# DMX_RP2040.net
KiCad netlist of a schematic drawn in Altium Designer
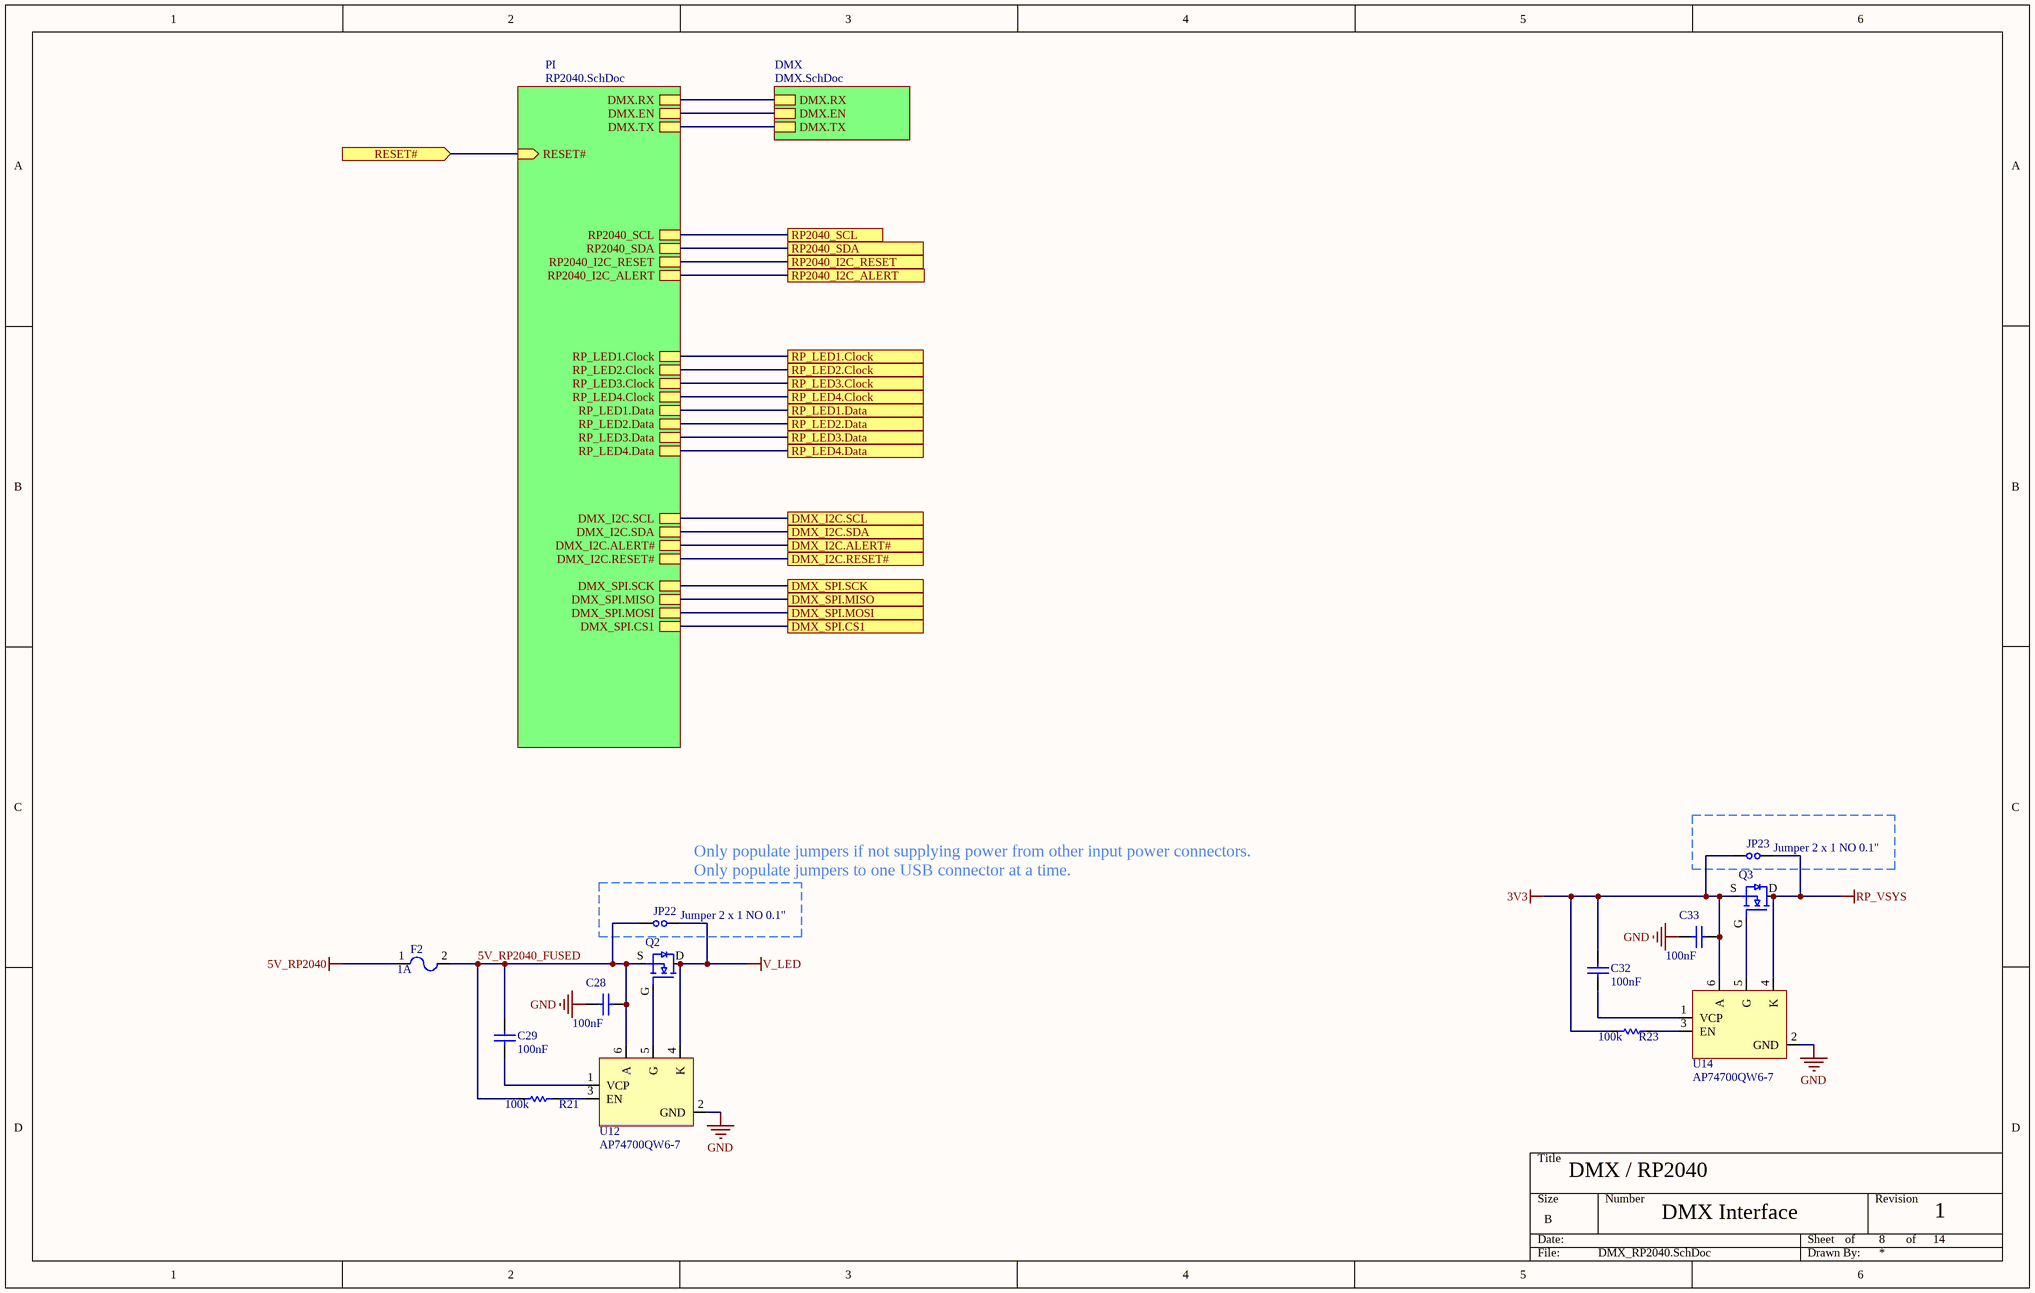
[diagram p0: DMX_RP2040.SchDoc]

(export (version "E")
  (design (tool "Eeschema 10.0.6"))
  (components
    (comp (ref "C28")
      (value "100nF")
      (footprint "CAPC1608X10N_0603_MED")
      (fields (field (name "Comment") "CC0603KRX7R0BB104"))
      (libsource (lib "Equus Computer Systems") (part "CAP-NP-2"))
    )
    (comp (ref "C29")
      (value "100nF")
      (footprint "CAPC1608X10N_0603_MED")
      (fields (field (name "Comment") "CC0603KRX7R0BB104"))
      (libsource (lib "Equus Computer Systems") (part "CAP-NP-2"))
    )
    (comp (ref "C32")
      (value "100nF")
      (footprint "CAPC1608X10N_0603_MED")
      (fields (field (name "Comment") "CC0603KRX7R0BB104"))
      (libsource (lib "Equus Computer Systems") (part "CAP-NP-2"))
    )
    (comp (ref "C33")
      (value "100nF")
      (footprint "CAPC1608X10N_0603_MED")
      (fields (field (name "Comment") "CC0603KRX7R0BB104"))
      (libsource (lib "Equus Computer Systems") (part "CAP-NP-2"))
    )
    (comp (ref "F2")
      (value "0ZCJ0100FF2E")
      (footprint "FUSE3216X04N_1206MED")
      (description "PTC Resettable Fuse, 6V, 0.055ohm, Surface Mount")
      (fields (field (name "CURRENT RATING") "1A"))
      (libsource (lib "Equus Computer Systems") (part "Fuse"))
    )
    (comp (ref "JP22")
      (value "Jumper 2 x 1 NO 0.1\"")
      (footprint "FP-M20-9990245-MFG")
      (libsource (lib "Equus Computer Systems") (part "Jumper 2 NO"))
    )
    (comp (ref "JP23")
      (value "Jumper 2 x 1 NO 0.1\"")
      (footprint "FP-M20-9990245-MFG")
      (libsource (lib "Equus Computer Systems") (part "Jumper 2 NO"))
    )
    (comp (ref "Q2")
      (value "DMN6075S-7")
      (footprint "FP-SOT23-MFG")
      (description "Single N-Channel 60 V 120 mOhm 12.3 nC 0.8 W Silicon Mosfet - SOT-23")
      (fields (field (name "POWER") "800mW"))
      (libsource (lib "Equus Computer Systems") (part "TRANS-MOSFET"))
    )
    (comp (ref "Q3")
      (value "DMN6075S-7")
      (footprint "FP-SOT23-MFG")
      (description "Single N-Channel 60 V 120 mOhm 12.3 nC 0.8 W Silicon Mosfet - SOT-23")
      (fields (field (name "POWER") "800mW"))
      (libsource (lib "Equus Computer Systems") (part "TRANS-MOSFET"))
    )
    (comp (ref "R21")
      (value "100k")
      (footprint "RESC1608X06N_0603_MED")
      (fields
        (field (name "POWER") "100mW")
        (field (name "TOLERANCE") "0.5%")
        (field (name "Comment") "RC0603DR-07100KL")
      )
      (libsource (lib "Equus Computer Systems") (part "RES-2"))
    )
    (comp (ref "R23")
      (value "100k")
      (footprint "RESC1608X06N_0603_MED")
      (fields
        (field (name "POWER") "100mW")
        (field (name "TOLERANCE") "0.5%")
        (field (name "Comment") "RC0603DR-07100KL")
      )
      (libsource (lib "Equus Computer Systems") (part "RES-2"))
    )
    (comp (ref "U12")
      (value "AP74700QW6-7")
      (footprint "SOT95P285X130-6N")
      (description "ORController N-Channel Single Automotive AEC-Q100 6-Pin SOT-26 T/R")
      (libsource (lib "Equus Computer Systems") (part "AP74700QW6-7-Symbol-1"))
    )
    (comp (ref "U14")
      (value "AP74700QW6-7")
      (footprint "SOT95P285X130-6N")
      (description "ORController N-Channel Single Automotive AEC-Q100 6-Pin SOT-26 T/R")
      (libsource (lib "Equus Computer Systems") (part "AP74700QW6-7-Symbol-1"))
    )
  )
  (nets
    (net (code "1") (name "/5V_RP2040_FUSED") (class "Default")
      (node (ref "C28") (pin "1") (pinfunction "1_1") (pintype "passive"))
      (node (ref "C29") (pin "2") (pinfunction "2_2") (pintype "passive"))
      (node (ref "F2") (pin "2") (pinfunction "2_2") (pintype "passive"))
      (node (ref "JP22") (pin "1") (pinfunction "1_1") (pintype "passive"))
      (node (ref "Q2") (pin "S") (pinfunction "S_S") (pintype "passive"))
      (node (ref "R21") (pin "1") (pinfunction "1_1") (pintype "passive"))
      (node (ref "U12") (pin "6") (pinfunction "A_6") (pintype "passive"))
    )
    (net (code "26") (name "3V3") (class "Default")
      (node (ref "C32") (pin "2") (pinfunction "2_2") (pintype "passive"))
      (node (ref "C33") (pin "1") (pinfunction "1_1") (pintype "passive"))
      (node (ref "JP23") (pin "1") (pinfunction "1_1") (pintype "passive"))
      (node (ref "Q3") (pin "S") (pinfunction "S_S") (pintype "passive"))
      (node (ref "R23") (pin "2") (pinfunction "2_2") (pintype "passive"))
      (node (ref "U14") (pin "6") (pinfunction "A_6") (pintype "passive"))
    )
    (net (code "27") (name "5V_RP2040") (class "Default")
      (node (ref "F2") (pin "1") (pinfunction "1_1") (pintype "passive"))
    )
    (net (code "28") (name "GND") (class "Default")
      (node (ref "C28") (pin "2") (pinfunction "2_2") (pintype "passive"))
      (node (ref "C33") (pin "2") (pinfunction "2_2") (pintype "passive"))
      (node (ref "U12") (pin "2") (pinfunction "GND_2") (pintype "passive"))
      (node (ref "U14") (pin "2") (pinfunction "GND_2") (pintype "passive"))
    )
    (net (code "29") (name "Net-(U12-EN)") (class "Default")
      (node (ref "R21") (pin "2") (pinfunction "2_2") (pintype "passive"))
      (node (ref "U12") (pin "3") (pinfunction "EN_3") (pintype "passive"))
    )
    (net (code "30") (name "Net-(U12-G)") (class "Default")
      (node (ref "Q2") (pin "G") (pinfunction "G_G") (pintype "passive"))
      (node (ref "U12") (pin "5") (pinfunction "G_5") (pintype "passive"))
    )
    (net (code "31") (name "Net-(U12-VCP)") (class "Default")
      (node (ref "C29") (pin "1") (pinfunction "1_1") (pintype "passive"))
      (node (ref "U12") (pin "1") (pinfunction "VCP_1") (pintype "passive"))
    )
    (net (code "32") (name "Net-(U14-EN)") (class "Default")
      (node (ref "R23") (pin "1") (pinfunction "1_1") (pintype "passive"))
      (node (ref "U14") (pin "3") (pinfunction "EN_3") (pintype "passive"))
    )
    (net (code "33") (name "Net-(U14-G)") (class "Default")
      (node (ref "Q3") (pin "G") (pinfunction "G_G") (pintype "passive"))
      (node (ref "U14") (pin "5") (pinfunction "G_5") (pintype "passive"))
    )
    (net (code "34") (name "Net-(U14-VCP)") (class "Default")
      (node (ref "C32") (pin "1") (pinfunction "1_1") (pintype "passive"))
      (node (ref "U14") (pin "1") (pinfunction "VCP_1") (pintype "passive"))
    )
    (net (code "35") (name "RP_VSYS") (class "Default")
      (node (ref "JP23") (pin "2") (pinfunction "2_2") (pintype "passive"))
      (node (ref "Q3") (pin "D") (pinfunction "D_D") (pintype "passive"))
      (node (ref "U14") (pin "4") (pinfunction "K_4") (pintype "passive"))
    )
    (net (code "36") (name "V_LED") (class "Default")
      (node (ref "JP22") (pin "2") (pinfunction "2_2") (pintype "passive"))
      (node (ref "Q2") (pin "D") (pinfunction "D_D") (pintype "passive"))
      (node (ref "U12") (pin "4") (pinfunction "K_4") (pintype "passive"))
    )
  )
)
